# Xadow_IO.net
KiCad netlist of a schematic drawn in EAGLE
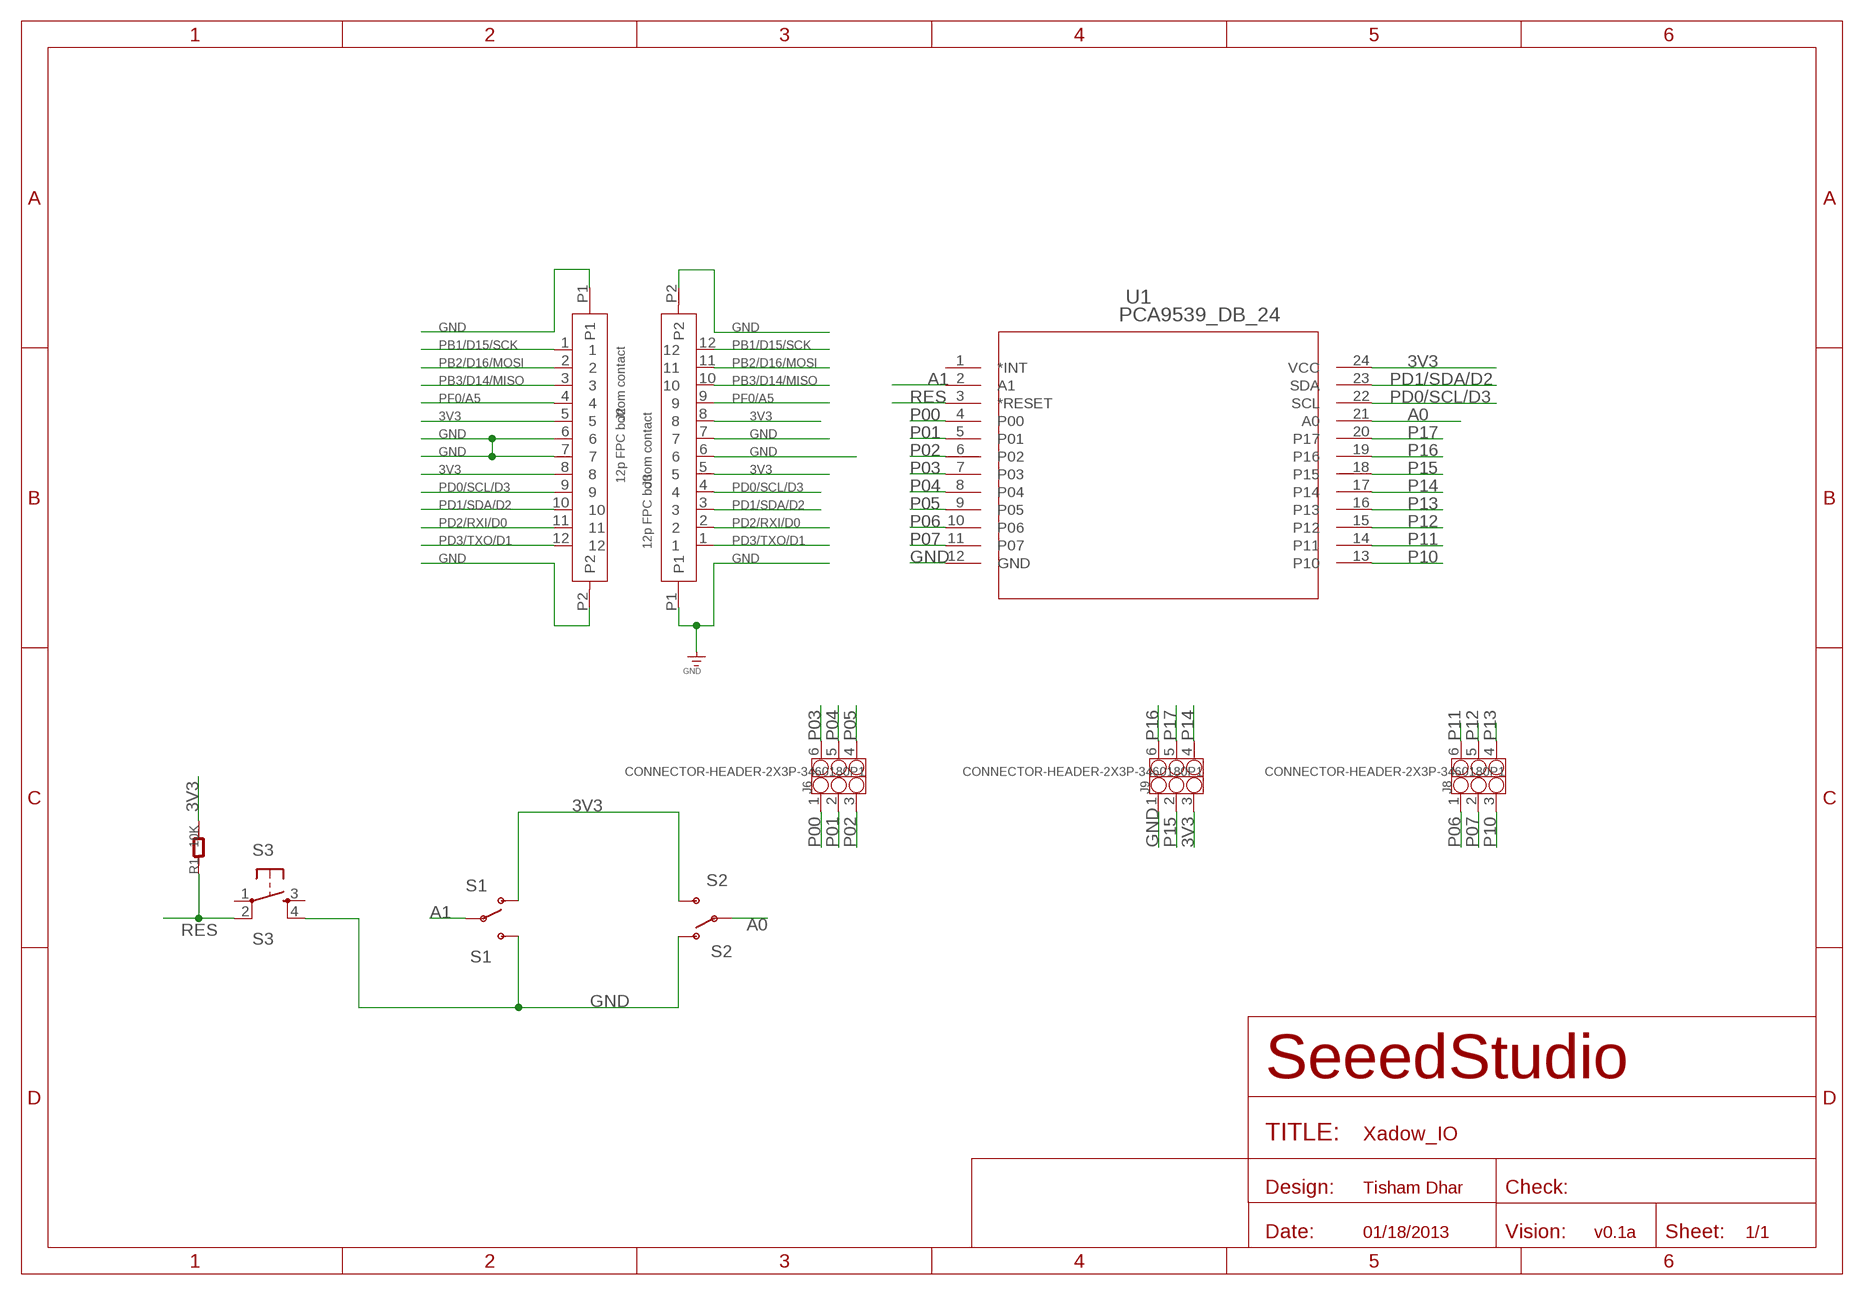
[diagram p0: schematic, sheet 1]

(export (version "E")
  (design (tool "Eeschema 10.0.6"))
  (components
    (comp (ref "J2")
      (value "12p FPC bottom contact")
      (footprint "eagle-import:12P-0.5")
      (libsource (lib "eagle-import") (part "FPC052002-12LT"))
    )
    (comp (ref "J3")
      (value "12p FPC bottom contact")
      (footprint "eagle-import:12P-0.5")
      (libsource (lib "eagle-import") (part "FPC052002-12LT"))
    )
    (comp (ref "J6")
      (value "CONNECTOR-HEADER-2X3P-3460180P1")
      (footprint "eagle-import:2X3P-2.54-2.54-11.6-3.0-BLACK-MALE")
      (libsource (lib "eagle-import") (part "CONNECTOR-HEADER-2X3P-3460180P1"))
    )
    (comp (ref "J8")
      (value "CONNECTOR-HEADER-2X3P-3460180P1")
      (footprint "eagle-import:2X3P-2.54-2.54-11.6-3.0-BLACK-MALE")
      (libsource (lib "eagle-import") (part "CONNECTOR-HEADER-2X3P-3460180P1"))
    )
    (comp (ref "J9")
      (value "CONNECTOR-HEADER-2X3P-3460180P1")
      (footprint "eagle-import:2X3P-2.54-2.54-11.6-3.0-BLACK-MALE")
      (libsource (lib "eagle-import") (part "CONNECTOR-HEADER-2X3P-3460180P1"))
    )
    (comp (ref "R1")
      (value "10K")
      (footprint "eagle-import:R0603")
      (libsource (lib "eagle-import") (part "R-0603"))
    )
    (comp (ref "S1")
      (value "S1")
      (footprint "eagle-import:SWITCH-SPST-SMD-A")
      (libsource (lib "eagle-import") (part "SWITCH-SPDT-SMD-A"))
    )
    (comp (ref "S2")
      (value "S2")
      (footprint "eagle-import:SWITCH-SPST-SMD-A")
      (libsource (lib "eagle-import") (part "SWITCH-SPDT-SMD-A"))
    )
    (comp (ref "S3")
      (value "S3")
      (footprint "eagle-import:TACTILE_SWITCH_SMD")
      (libsource (lib "eagle-import") (part "TAC_SWITCHSMD"))
    )
    (comp (ref "U1")
      (value "PCA9539_DB_24")
      (footprint "eagle-import:DB24")
      (fields
        (field (name "GENERIC_PART_NUMBER") "PCA9539")
        (field (name "MANUFACTURER") "Texas Instruments")
        (field (name "MANUFACTURER_PART_NUMBER") "pca9539_db_24")
      )
      (libsource (lib "eagle-import") (part "PCA9539_DB_24"))
    )
  )
  (nets
    (net (code "1") (name "/3V3") (class "Default")
      (node (ref "J2") (pin "5") (pinfunction "5_5") (pintype "bidirectional"))
      (node (ref "J2") (pin "8") (pinfunction "8_8") (pintype "bidirectional"))
      (node (ref "J3") (pin "5") (pinfunction "5_5") (pintype "bidirectional"))
      (node (ref "J3") (pin "8") (pinfunction "8_8") (pintype "bidirectional"))
      (node (ref "J9") (pin "3") (pinfunction "3_3") (pintype "bidirectional"))
      (node (ref "R1") (pin "2") (pinfunction "2_2") (pintype "bidirectional"))
      (node (ref "S1") (pin "1") (pinfunction "O_1") (pintype "passive"))
      (node (ref "S2") (pin "3") (pinfunction "S_3") (pintype "passive"))
      (node (ref "U1") (pin "24") (pinfunction "VCC_24") (pintype "power_in"))
    )
    (net (code "2") (name "/A0") (class "Default")
      (node (ref "S2") (pin "2") (pinfunction "P_2") (pintype "passive"))
      (node (ref "U1") (pin "21") (pinfunction "A0_21") (pintype "input"))
    )
    (net (code "3") (name "/A1") (class "Default")
      (node (ref "S1") (pin "2") (pinfunction "P_2") (pintype "passive"))
      (node (ref "U1") (pin "2") (pinfunction "A1_2") (pintype "input"))
    )
    (net (code "4") (name "/P00") (class "Default")
      (node (ref "J6") (pin "1") (pinfunction "1_1") (pintype "bidirectional"))
      (node (ref "U1") (pin "4") (pinfunction "P00_4") (pintype "bidirectional"))
    )
    (net (code "5") (name "/P01") (class "Default")
      (node (ref "J6") (pin "2") (pinfunction "2_2") (pintype "bidirectional"))
      (node (ref "U1") (pin "5") (pinfunction "P01_5") (pintype "bidirectional"))
    )
    (net (code "6") (name "/P02") (class "Default")
      (node (ref "J6") (pin "3") (pinfunction "3_3") (pintype "bidirectional"))
      (node (ref "U1") (pin "6") (pinfunction "P02_6") (pintype "bidirectional"))
    )
    (net (code "7") (name "/P03") (class "Default")
      (node (ref "J6") (pin "6") (pinfunction "6_6") (pintype "bidirectional"))
      (node (ref "U1") (pin "7") (pinfunction "P03_7") (pintype "bidirectional"))
    )
    (net (code "8") (name "/P04") (class "Default")
      (node (ref "J6") (pin "5") (pinfunction "5_5") (pintype "bidirectional"))
      (node (ref "U1") (pin "8") (pinfunction "P04_8") (pintype "bidirectional"))
    )
    (net (code "9") (name "/P05") (class "Default")
      (node (ref "J6") (pin "4") (pinfunction "4_4") (pintype "bidirectional"))
      (node (ref "U1") (pin "9") (pinfunction "P05_9") (pintype "bidirectional"))
    )
    (net (code "10") (name "/P06") (class "Default")
      (node (ref "J8") (pin "1") (pinfunction "1_1") (pintype "bidirectional"))
      (node (ref "U1") (pin "10") (pinfunction "P06_10") (pintype "bidirectional"))
    )
    (net (code "11") (name "/P07") (class "Default")
      (node (ref "J8") (pin "2") (pinfunction "2_2") (pintype "bidirectional"))
      (node (ref "U1") (pin "11") (pinfunction "P07_11") (pintype "bidirectional"))
    )
    (net (code "12") (name "/P10") (class "Default")
      (node (ref "J8") (pin "3") (pinfunction "3_3") (pintype "bidirectional"))
      (node (ref "U1") (pin "13") (pinfunction "P10_13") (pintype "bidirectional"))
    )
    (net (code "13") (name "/P11") (class "Default")
      (node (ref "J8") (pin "6") (pinfunction "6_6") (pintype "bidirectional"))
      (node (ref "U1") (pin "14") (pinfunction "P11_14") (pintype "bidirectional"))
    )
    (net (code "14") (name "/P12") (class "Default")
      (node (ref "J8") (pin "5") (pinfunction "5_5") (pintype "bidirectional"))
      (node (ref "U1") (pin "15") (pinfunction "P12_15") (pintype "bidirectional"))
    )
    (net (code "15") (name "/P13") (class "Default")
      (node (ref "J8") (pin "4") (pinfunction "4_4") (pintype "bidirectional"))
      (node (ref "U1") (pin "16") (pinfunction "P13_16") (pintype "bidirectional"))
    )
    (net (code "16") (name "/P14") (class "Default")
      (node (ref "J9") (pin "4") (pinfunction "4_4") (pintype "bidirectional"))
      (node (ref "U1") (pin "17") (pinfunction "P14_17") (pintype "bidirectional"))
    )
    (net (code "17") (name "/P15") (class "Default")
      (node (ref "J9") (pin "2") (pinfunction "2_2") (pintype "bidirectional"))
      (node (ref "U1") (pin "18") (pinfunction "P15_18") (pintype "bidirectional"))
    )
    (net (code "18") (name "/P16") (class "Default")
      (node (ref "J9") (pin "6") (pinfunction "6_6") (pintype "bidirectional"))
      (node (ref "U1") (pin "19") (pinfunction "P16_19") (pintype "bidirectional"))
    )
    (net (code "19") (name "/P17") (class "Default")
      (node (ref "J9") (pin "5") (pinfunction "5_5") (pintype "bidirectional"))
      (node (ref "U1") (pin "20") (pinfunction "P17_20") (pintype "bidirectional"))
    )
    (net (code "20") (name "/PB1{slash}D15{slash}SCK") (class "Default")
      (node (ref "J2") (pin "1") (pinfunction "1_1") (pintype "bidirectional"))
      (node (ref "J3") (pin "12") (pinfunction "12_12") (pintype "bidirectional"))
    )
    (net (code "21") (name "/PB2{slash}D16{slash}MOSI") (class "Default")
      (node (ref "J2") (pin "2") (pinfunction "2_2") (pintype "bidirectional"))
      (node (ref "J3") (pin "11") (pinfunction "11_11") (pintype "bidirectional"))
    )
    (net (code "22") (name "/PB3{slash}D14{slash}MISO") (class "Default")
      (node (ref "J2") (pin "3") (pinfunction "3_3") (pintype "bidirectional"))
      (node (ref "J3") (pin "10") (pinfunction "10_10") (pintype "bidirectional"))
    )
    (net (code "23") (name "/PD0{slash}SCL{slash}D3") (class "Default")
      (node (ref "J2") (pin "9") (pinfunction "9_9") (pintype "bidirectional"))
      (node (ref "J3") (pin "4") (pinfunction "4_4") (pintype "bidirectional"))
      (node (ref "U1") (pin "22") (pinfunction "SCL_22") (pintype "passive"))
    )
    (net (code "24") (name "/PD1{slash}SDA{slash}D2") (class "Default")
      (node (ref "J2") (pin "10") (pinfunction "10_10") (pintype "bidirectional"))
      (node (ref "J3") (pin "3") (pinfunction "3_3") (pintype "bidirectional"))
      (node (ref "U1") (pin "23") (pinfunction "SDA_23") (pintype "passive"))
    )
    (net (code "25") (name "/PD2{slash}RXI{slash}D0") (class "Default")
      (node (ref "J2") (pin "11") (pinfunction "11_11") (pintype "bidirectional"))
      (node (ref "J3") (pin "2") (pinfunction "2_2") (pintype "bidirectional"))
    )
    (net (code "26") (name "/PD3{slash}TXO{slash}D1") (class "Default")
      (node (ref "J2") (pin "12") (pinfunction "12_12") (pintype "bidirectional"))
      (node (ref "J3") (pin "1") (pinfunction "1_1") (pintype "bidirectional"))
    )
    (net (code "27") (name "/PF0{slash}A5") (class "Default")
      (node (ref "J2") (pin "4") (pinfunction "4_4") (pintype "bidirectional"))
      (node (ref "J3") (pin "9") (pinfunction "9_9") (pintype "bidirectional"))
    )
    (net (code "28") (name "/RES") (class "Default")
      (node (ref "R1") (pin "1") (pinfunction "1_1") (pintype "bidirectional"))
      (node (ref "S3") (pin "2") (pinfunction "2_2") (pintype "passive"))
      (node (ref "U1") (pin "3") (pinfunction "*RESET_3") (pintype "input"))
    )
    (net (code "29") (name "GND") (class "Default")
      (node (ref "J2") (pin "6") (pinfunction "6_6") (pintype "bidirectional"))
      (node (ref "J2") (pin "7") (pinfunction "7_7") (pintype "bidirectional"))
      (node (ref "J2") (pin "P1") (pinfunction "P1_P1") (pintype "bidirectional"))
      (node (ref "J2") (pin "P2") (pinfunction "P2_P2") (pintype "bidirectional"))
      (node (ref "J3") (pin "6") (pinfunction "6_6") (pintype "bidirectional"))
      (node (ref "J3") (pin "7") (pinfunction "7_7") (pintype "bidirectional"))
      (node (ref "J3") (pin "P1") (pinfunction "P1_P1") (pintype "bidirectional"))
      (node (ref "J3") (pin "P2") (pinfunction "P2_P2") (pintype "bidirectional"))
      (node (ref "J9") (pin "1") (pinfunction "1_1") (pintype "bidirectional"))
      (node (ref "S1") (pin "3") (pinfunction "S_3") (pintype "passive"))
      (node (ref "S2") (pin "1") (pinfunction "O_1") (pintype "passive"))
      (node (ref "S3") (pin "4") (pinfunction "4_4") (pintype "passive"))
      (node (ref "U1") (pin "12") (pinfunction "GND_12") (pintype "power_in"))
    )
    (net (code "30") (name "unconnected-(S3-Pad1)") (class "Default")
      (node (ref "S3") (pin "1") (pinfunction "1_1") (pintype "passive"))
    )
    (net (code "31") (name "unconnected-(S3-Pad3)") (class "Default")
      (node (ref "S3") (pin "3") (pinfunction "3_3") (pintype "passive"))
    )
    (net (code "32") (name "unconnected-(U1-*INT-Pad1)") (class "Default")
      (node (ref "U1") (pin "1") (pinfunction "*INT_1") (pintype "output"))
    )
  )
)
